# H3_MIDISmallController_Rev_1.net
KiCad netlist of a schematic drawn in EAGLE
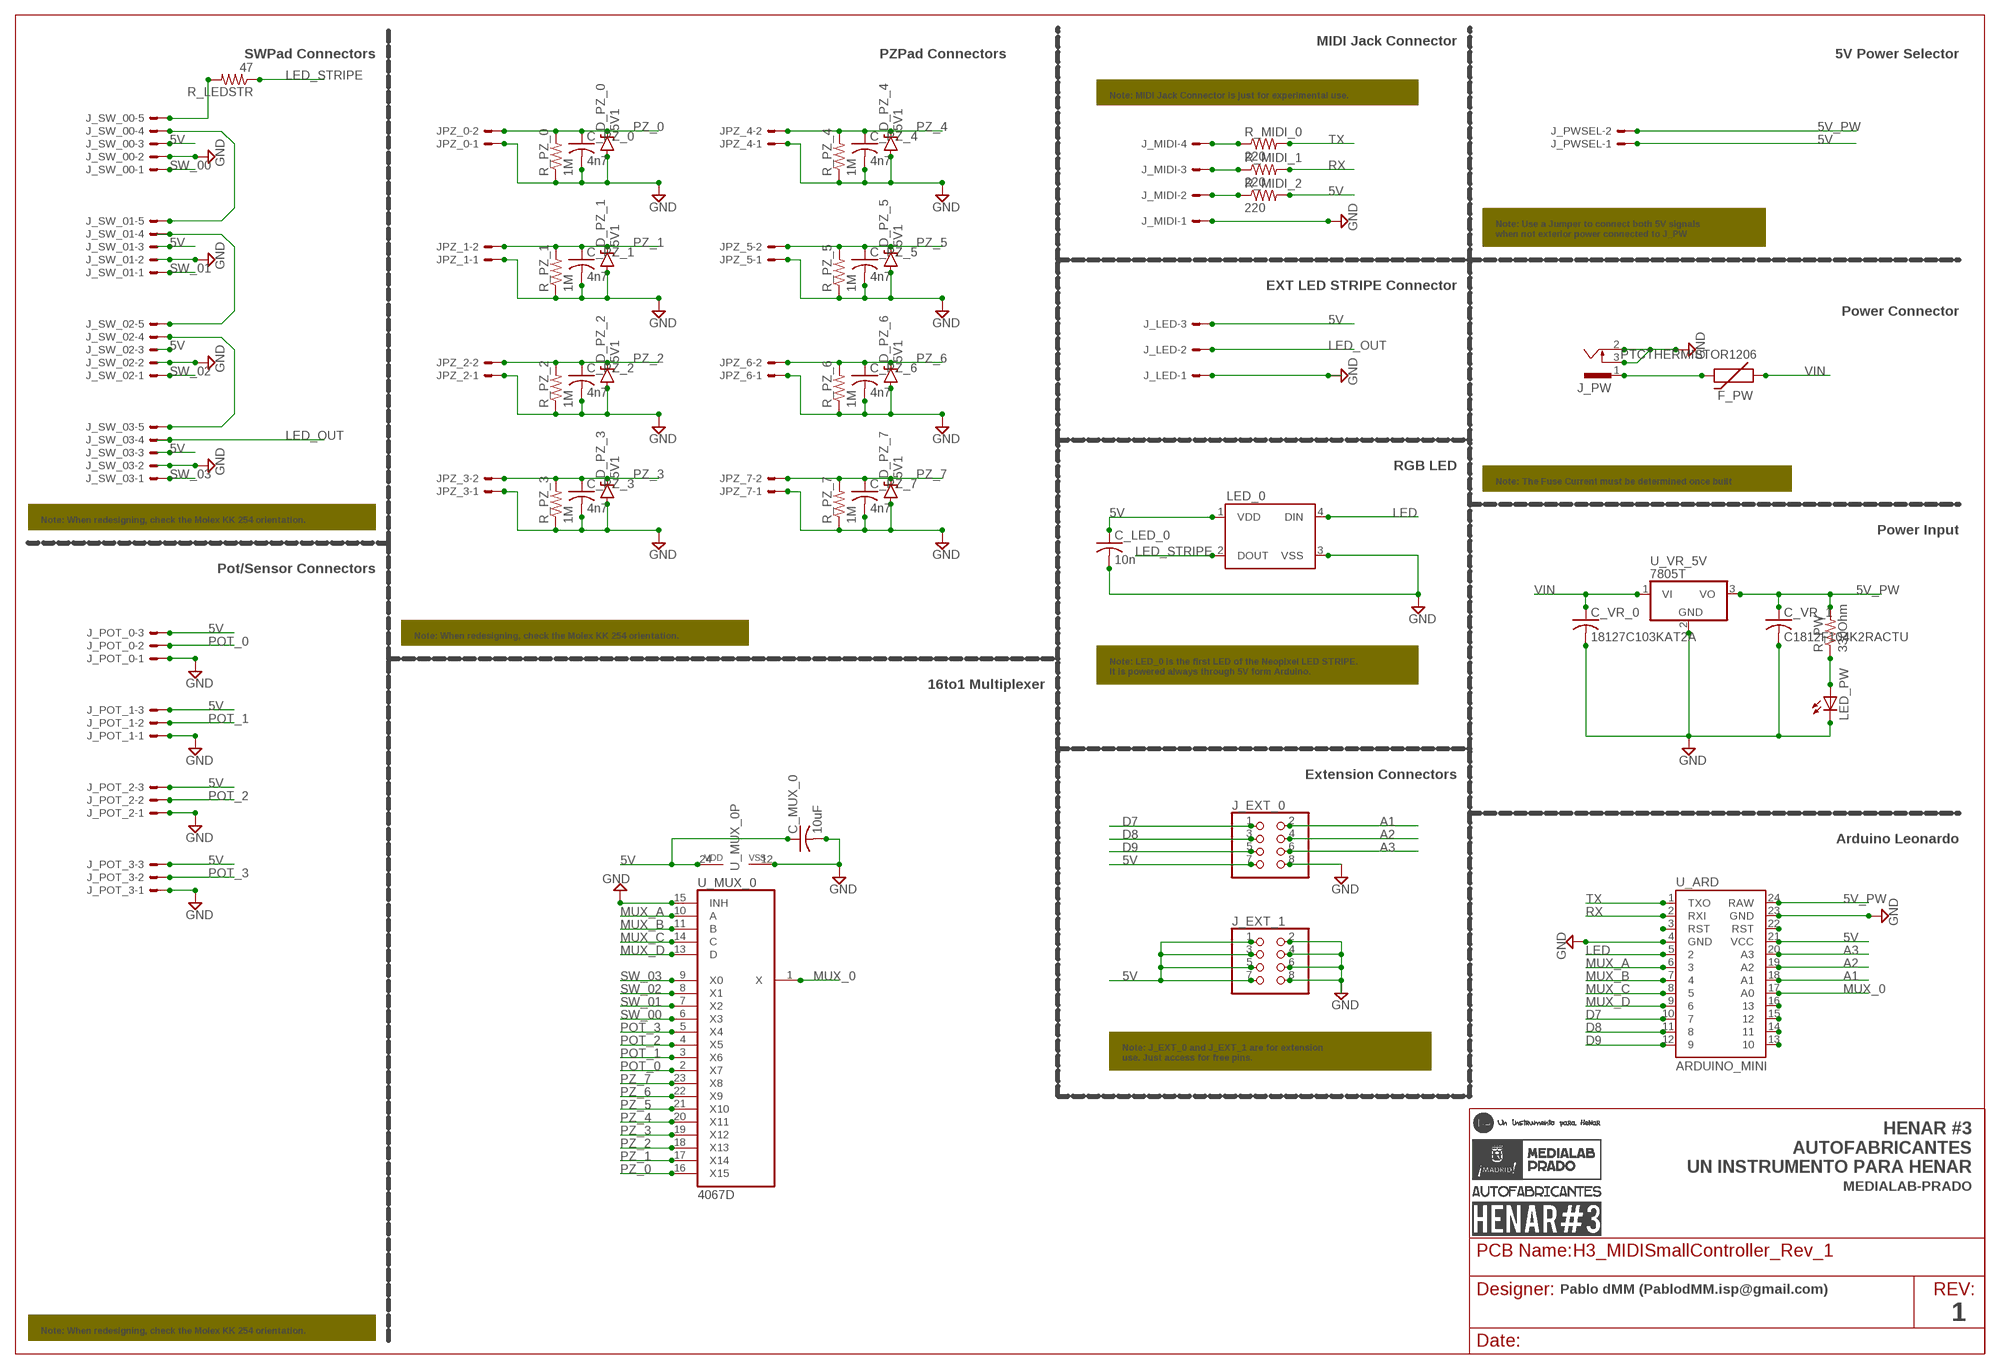
[diagram p0: schematic, sheet 1]

(export (version "E")
  (design (tool "Eeschema 10.0.6"))
  (components
    (comp (ref "C_LED_0")
      (value "10n")
      (footprint "eagle-import:C1206")
      (libsource (lib "eagle-import") (part "C-USC1206"))
    )
    (comp (ref "C_MUX_0")
      (value "10uF")
      (footprint "eagle-import:C1206K")
      (libsource (lib "eagle-import") (part "C-USC1206K"))
    )
    (comp (ref "C_PZ_0")
      (value "4n7")
      (footprint "eagle-import:C1206")
      (libsource (lib "eagle-import") (part "C-USC1206"))
    )
    (comp (ref "C_PZ_1")
      (value "4n7")
      (footprint "eagle-import:C1206")
      (libsource (lib "eagle-import") (part "C-USC1206"))
    )
    (comp (ref "C_PZ_2")
      (value "4n7")
      (footprint "eagle-import:C1206")
      (libsource (lib "eagle-import") (part "C-USC1206"))
    )
    (comp (ref "C_PZ_3")
      (value "4n7")
      (footprint "eagle-import:C1206")
      (libsource (lib "eagle-import") (part "C-USC1206"))
    )
    (comp (ref "C_PZ_4")
      (value "4n7")
      (footprint "eagle-import:C1206")
      (libsource (lib "eagle-import") (part "C-USC1206"))
    )
    (comp (ref "C_PZ_5")
      (value "4n7")
      (footprint "eagle-import:C1206")
      (libsource (lib "eagle-import") (part "C-USC1206"))
    )
    (comp (ref "C_PZ_6")
      (value "4n7")
      (footprint "eagle-import:C1206")
      (libsource (lib "eagle-import") (part "C-USC1206"))
    )
    (comp (ref "C_PZ_7")
      (value "4n7")
      (footprint "eagle-import:C1206")
      (libsource (lib "eagle-import") (part "C-USC1206"))
    )
    (comp (ref "C_VR_0")
      (value "18127C103KAT2A")
      (footprint "eagle-import:C1206")
      (libsource (lib "eagle-import") (part "C-USC1206"))
    )
    (comp (ref "C_VR_1")
      (value "C1812F104K2RACTU")
      (footprint "eagle-import:C1206")
      (libsource (lib "eagle-import") (part "C-USC1206"))
    )
    (comp (ref "D_PZ_0")
      (value "5V1")
      (footprint "eagle-import:DIODE-BZT52")
      (libsource (lib "eagle-import") (part "DIODE-ZENER"))
    )
    (comp (ref "D_PZ_1")
      (value "5V1")
      (footprint "eagle-import:DIODE-BZT52")
      (libsource (lib "eagle-import") (part "DIODE-ZENER"))
    )
    (comp (ref "D_PZ_2")
      (value "5V1")
      (footprint "eagle-import:DIODE-BZT52")
      (libsource (lib "eagle-import") (part "DIODE-ZENER"))
    )
    (comp (ref "D_PZ_3")
      (value "5V1")
      (footprint "eagle-import:DIODE-BZT52")
      (libsource (lib "eagle-import") (part "DIODE-ZENER"))
    )
    (comp (ref "D_PZ_4")
      (value "5V1")
      (footprint "eagle-import:DIODE-BZT52")
      (libsource (lib "eagle-import") (part "DIODE-ZENER"))
    )
    (comp (ref "D_PZ_5")
      (value "5V1")
      (footprint "eagle-import:DIODE-BZT52")
      (libsource (lib "eagle-import") (part "DIODE-ZENER"))
    )
    (comp (ref "D_PZ_6")
      (value "5V1")
      (footprint "eagle-import:DIODE-BZT52")
      (libsource (lib "eagle-import") (part "DIODE-ZENER"))
    )
    (comp (ref "D_PZ_7")
      (value "5V1")
      (footprint "eagle-import:DIODE-BZT52")
      (libsource (lib "eagle-import") (part "DIODE-ZENER"))
    )
    (comp (ref "F_PW")
      (value "PTCTHERMISTOR1206")
      (footprint "eagle-import:PTC-1206")
      (libsource (lib "eagle-import") (part "PTCTHERMISTOR1206"))
    )
    (comp (ref "JPZ_0")
      (value "22-05-7028-02")
      (footprint "eagle-import:7395-02")
      (libsource (lib "eagle-import") (part "22-?-0205-7028"))
    )
    (comp (ref "JPZ_1")
      (value "22-05-7028-02")
      (footprint "eagle-import:7395-02")
      (libsource (lib "eagle-import") (part "22-?-0205-7028"))
    )
    (comp (ref "JPZ_2")
      (value "22-05-7028-02")
      (footprint "eagle-import:7395-02")
      (libsource (lib "eagle-import") (part "22-?-0205-7028"))
    )
    (comp (ref "JPZ_3")
      (value "22-05-7028-02")
      (footprint "eagle-import:7395-02")
      (libsource (lib "eagle-import") (part "22-?-0205-7028"))
    )
    (comp (ref "JPZ_4")
      (value "22-05-7028-02")
      (footprint "eagle-import:7395-02")
      (libsource (lib "eagle-import") (part "22-?-0205-7028"))
    )
    (comp (ref "JPZ_5")
      (value "22-05-7028-02")
      (footprint "eagle-import:7395-02")
      (libsource (lib "eagle-import") (part "22-?-0205-7028"))
    )
    (comp (ref "JPZ_6")
      (value "22-05-7028-02")
      (footprint "eagle-import:7395-02")
      (libsource (lib "eagle-import") (part "22-?-0205-7028"))
    )
    (comp (ref "JPZ_7")
      (value "22-05-7028-02")
      (footprint "eagle-import:7395-02")
      (libsource (lib "eagle-import") (part "22-?-0205-7028"))
    )
    (comp (ref "J_EXT_0")
      (value "PINHD-2X4/90")
      (footprint "eagle-import:2X04_90")
      (libsource (lib "eagle-import") (part "PINHD-2X4/90"))
    )
    (comp (ref "J_EXT_1")
      (value "PINHD-2X4/90")
      (footprint "eagle-import:2X04_90")
      (libsource (lib "eagle-import") (part "PINHD-2X4/90"))
    )
    (comp (ref "J_LED")
      (value "22-05-7038-03")
      (footprint "eagle-import:7395-03")
      (libsource (lib "eagle-import") (part "22-?-0305-7038"))
    )
    (comp (ref "J_MIDI")
      (value "22-05-7048-04")
      (footprint "eagle-import:7395-04")
      (libsource (lib "eagle-import") (part "22-?-0405-7048"))
    )
    (comp (ref "J_POT_0")
      (value "22-05-7038-03")
      (footprint "eagle-import:7395-03")
      (libsource (lib "eagle-import") (part "22-?-0305-7038"))
    )
    (comp (ref "J_POT_1")
      (value "22-05-7038-03")
      (footprint "eagle-import:7395-03")
      (libsource (lib "eagle-import") (part "22-?-0305-7038"))
    )
    (comp (ref "J_POT_2")
      (value "22-05-7038-03")
      (footprint "eagle-import:7395-03")
      (libsource (lib "eagle-import") (part "22-?-0305-7038"))
    )
    (comp (ref "J_POT_3")
      (value "22-05-7038-03")
      (footprint "eagle-import:7395-03")
      (libsource (lib "eagle-import") (part "22-?-0305-7038"))
    )
    (comp (ref "J_PW")
      (value "SCD-014A")
      (footprint "eagle-import:SCD-014-A")
      (libsource (lib "eagle-import") (part "SCD-014A"))
    )
    (comp (ref "J_PWSEL")
      (value "22-05-7028-02")
      (footprint "eagle-import:7395-02")
      (libsource (lib "eagle-import") (part "22-?-0205-7028"))
    )
    (comp (ref "J_SW_00")
      (value "22-05-7058-05")
      (footprint "eagle-import:7395-05")
      (libsource (lib "eagle-import") (part "22-?-0505-7058"))
    )
    (comp (ref "J_SW_01")
      (value "22-05-7058-05")
      (footprint "eagle-import:7395-05")
      (libsource (lib "eagle-import") (part "22-?-0505-7058"))
    )
    (comp (ref "J_SW_02")
      (value "22-05-7058-05")
      (footprint "eagle-import:7395-05")
      (libsource (lib "eagle-import") (part "22-?-0505-7058"))
    )
    (comp (ref "J_SW_03")
      (value "22-05-7058-05")
      (footprint "eagle-import:7395-05")
      (libsource (lib "eagle-import") (part "22-?-0505-7058"))
    )
    (comp (ref "LED_0")
      (value "WS2812B")
      (footprint "eagle-import:WS2812B")
      (libsource (lib "eagle-import") (part "WS2812B"))
    )
    (comp (ref "LED_PW")
      (value "LEDSMT1206")
      (footprint "eagle-import:1206")
      (libsource (lib "eagle-import") (part "LEDSMT1206"))
    )
    (comp (ref "R_LEDSTR")
      (value "47")
      (footprint "eagle-import:M1206")
      (libsource (lib "eagle-import") (part "R-US_M1206"))
    )
    (comp (ref "R_MIDI_0")
      (value "220")
      (footprint "eagle-import:M1206")
      (libsource (lib "eagle-import") (part "R-US_M1206"))
    )
    (comp (ref "R_MIDI_1")
      (value "220")
      (footprint "eagle-import:M1206")
      (libsource (lib "eagle-import") (part "R-US_M1206"))
    )
    (comp (ref "R_MIDI_2")
      (value "220")
      (footprint "eagle-import:M1206")
      (libsource (lib "eagle-import") (part "R-US_M1206"))
    )
    (comp (ref "R_PW")
      (value "330Ohm")
      (footprint "eagle-import:M1206")
      (libsource (lib "eagle-import") (part "R-US_M1206"))
    )
    (comp (ref "R_PZ_0")
      (value "1M")
      (footprint "eagle-import:M1206")
      (libsource (lib "eagle-import") (part "R-US_M1206"))
    )
    (comp (ref "R_PZ_1")
      (value "1M")
      (footprint "eagle-import:M1206")
      (libsource (lib "eagle-import") (part "R-US_M1206"))
    )
    (comp (ref "R_PZ_2")
      (value "1M")
      (footprint "eagle-import:M1206")
      (libsource (lib "eagle-import") (part "R-US_M1206"))
    )
    (comp (ref "R_PZ_3")
      (value "1M")
      (footprint "eagle-import:M1206")
      (libsource (lib "eagle-import") (part "R-US_M1206"))
    )
    (comp (ref "R_PZ_4")
      (value "1M")
      (footprint "eagle-import:M1206")
      (libsource (lib "eagle-import") (part "R-US_M1206"))
    )
    (comp (ref "R_PZ_5")
      (value "1M")
      (footprint "eagle-import:M1206")
      (libsource (lib "eagle-import") (part "R-US_M1206"))
    )
    (comp (ref "R_PZ_6")
      (value "1M")
      (footprint "eagle-import:M1206")
      (libsource (lib "eagle-import") (part "R-US_M1206"))
    )
    (comp (ref "R_PZ_7")
      (value "1M")
      (footprint "eagle-import:M1206")
      (libsource (lib "eagle-import") (part "R-US_M1206"))
    )
    (comp (ref "U_ARD")
      (value "ARDUINO_MINI")
      (footprint "eagle-import:ARDUINO_MINI")
      (libsource (lib "eagle-import") (part "ARDUINO_MINI"))
    )
    (comp (ref "U_MUX_0")
      (value "4067D")
      (footprint "eagle-import:SO24W")
      (libsource (lib "eagle-import") (part "4067D"))
    )
    (comp (ref "U_VR_5V")
      (value "7805T")
      (footprint "eagle-import:TO220H")
      (libsource (lib "eagle-import") (part "78T05"))
    )
  )
  (nets
    (net (code "1") (name "/5V") (class "Default")
      (node (ref "C_LED_0") (pin "1") (pinfunction "1_1") (pintype "passive"))
      (node (ref "C_MUX_0") (pin "1") (pinfunction "1_1") (pintype "passive"))
      (node (ref "J_EXT_0") (pin "7") (pinfunction "7_7") (pintype "passive"))
      (node (ref "J_EXT_1") (pin "1") (pinfunction "1_1") (pintype "passive"))
      (node (ref "J_EXT_1") (pin "3") (pinfunction "3_3") (pintype "passive"))
      (node (ref "J_EXT_1") (pin "5") (pinfunction "5_5") (pintype "passive"))
      (node (ref "J_EXT_1") (pin "7") (pinfunction "7_7") (pintype "passive"))
      (node (ref "J_LED") (pin "3") (pinfunction "S_3") (pintype "passive"))
      (node (ref "J_POT_0") (pin "3") (pinfunction "S_3") (pintype "passive"))
      (node (ref "J_POT_1") (pin "3") (pinfunction "S_3") (pintype "passive"))
      (node (ref "J_POT_2") (pin "3") (pinfunction "S_3") (pintype "passive"))
      (node (ref "J_POT_3") (pin "3") (pinfunction "S_3") (pintype "passive"))
      (node (ref "J_PWSEL") (pin "1") (pinfunction "S_1") (pintype "passive"))
      (node (ref "J_SW_00") (pin "3") (pinfunction "S_3") (pintype "passive"))
      (node (ref "J_SW_01") (pin "3") (pinfunction "S_3") (pintype "passive"))
      (node (ref "J_SW_02") (pin "3") (pinfunction "S_3") (pintype "passive"))
      (node (ref "J_SW_03") (pin "3") (pinfunction "S_3") (pintype "passive"))
      (node (ref "LED_0") (pin "1") (pinfunction "VDD_1") (pintype "power_in"))
      (node (ref "R_MIDI_2") (pin "2") (pinfunction "2_2") (pintype "passive"))
      (node (ref "U_ARD") (pin "21") (pinfunction "VCC_21") (pintype "bidirectional"))
      (node (ref "U_MUX_0") (pin "24") (pinfunction "VDD_24") (pintype "power_in"))
    )
    (net (code "2") (name "/5V_PW") (class "Default")
      (node (ref "C_VR_1") (pin "1") (pinfunction "1_1") (pintype "passive"))
      (node (ref "J_PWSEL") (pin "2") (pinfunction "S_2") (pintype "passive"))
      (node (ref "R_PW") (pin "2") (pinfunction "2_2") (pintype "passive"))
      (node (ref "U_ARD") (pin "24") (pinfunction "RAW_24") (pintype "bidirectional"))
      (node (ref "U_VR_5V") (pin "3") (pinfunction "VO_3") (pintype "passive"))
    )
    (net (code "3") (name "/A1") (class "Default")
      (node (ref "J_EXT_0") (pin "2") (pinfunction "2_2") (pintype "passive"))
      (node (ref "U_ARD") (pin "18") (pinfunction "A1_18") (pintype "bidirectional"))
    )
    (net (code "4") (name "/A2") (class "Default")
      (node (ref "J_EXT_0") (pin "4") (pinfunction "4_4") (pintype "passive"))
      (node (ref "U_ARD") (pin "19") (pinfunction "A2_19") (pintype "bidirectional"))
    )
    (net (code "5") (name "/A3") (class "Default")
      (node (ref "J_EXT_0") (pin "6") (pinfunction "6_6") (pintype "passive"))
      (node (ref "U_ARD") (pin "20") (pinfunction "A3_20") (pintype "bidirectional"))
    )
    (net (code "6") (name "/D7") (class "Default")
      (node (ref "J_EXT_0") (pin "1") (pinfunction "1_1") (pintype "passive"))
      (node (ref "U_ARD") (pin "10") (pinfunction "7_10") (pintype "bidirectional"))
    )
    (net (code "7") (name "/D8") (class "Default")
      (node (ref "J_EXT_0") (pin "3") (pinfunction "3_3") (pintype "passive"))
      (node (ref "U_ARD") (pin "11") (pinfunction "8_11") (pintype "bidirectional"))
    )
    (net (code "8") (name "/D9") (class "Default")
      (node (ref "J_EXT_0") (pin "5") (pinfunction "5_5") (pintype "passive"))
      (node (ref "U_ARD") (pin "12") (pinfunction "9_12") (pintype "bidirectional"))
    )
    (net (code "9") (name "/LED") (class "Default")
      (node (ref "LED_0") (pin "4") (pinfunction "DIN_4") (pintype "input"))
      (node (ref "U_ARD") (pin "5") (pinfunction "2_5") (pintype "bidirectional"))
    )
    (net (code "10") (name "/LED_OUT") (class "Default")
      (node (ref "J_LED") (pin "2") (pinfunction "S_2") (pintype "passive"))
      (node (ref "J_SW_03") (pin "4") (pinfunction "S_4") (pintype "passive"))
    )
    (net (code "11") (name "/LED_STRIPE") (class "Default")
      (node (ref "LED_0") (pin "2") (pinfunction "DOUT_2") (pintype "output"))
      (node (ref "R_LEDSTR") (pin "1") (pinfunction "1_1") (pintype "passive"))
    )
    (net (code "12") (name "/MUX_0") (class "Default")
      (node (ref "U_ARD") (pin "17") (pinfunction "A0_17") (pintype "bidirectional"))
      (node (ref "U_MUX_0") (pin "1") (pinfunction "X_1") (pintype "output"))
    )
    (net (code "13") (name "/MUX_A") (class "Default")
      (node (ref "U_ARD") (pin "6") (pinfunction "3_6") (pintype "bidirectional"))
      (node (ref "U_MUX_0") (pin "10") (pinfunction "A_10") (pintype "input"))
    )
    (net (code "14") (name "/MUX_B") (class "Default")
      (node (ref "U_ARD") (pin "7") (pinfunction "4_7") (pintype "bidirectional"))
      (node (ref "U_MUX_0") (pin "11") (pinfunction "B_11") (pintype "input"))
    )
    (net (code "15") (name "/MUX_C") (class "Default")
      (node (ref "U_ARD") (pin "8") (pinfunction "5_8") (pintype "bidirectional"))
      (node (ref "U_MUX_0") (pin "14") (pinfunction "C_14") (pintype "input"))
    )
    (net (code "16") (name "/MUX_D") (class "Default")
      (node (ref "U_ARD") (pin "9") (pinfunction "6_9") (pintype "bidirectional"))
      (node (ref "U_MUX_0") (pin "13") (pinfunction "D_13") (pintype "input"))
    )
    (net (code "17") (name "/POT_0") (class "Default")
      (node (ref "J_POT_0") (pin "2") (pinfunction "S_2") (pintype "passive"))
      (node (ref "U_MUX_0") (pin "2") (pinfunction "X7_2") (pintype "input"))
    )
    (net (code "18") (name "/POT_1") (class "Default")
      (node (ref "J_POT_1") (pin "2") (pinfunction "S_2") (pintype "passive"))
      (node (ref "U_MUX_0") (pin "3") (pinfunction "X6_3") (pintype "input"))
    )
    (net (code "19") (name "/POT_2") (class "Default")
      (node (ref "J_POT_2") (pin "2") (pinfunction "S_2") (pintype "passive"))
      (node (ref "U_MUX_0") (pin "4") (pinfunction "X5_4") (pintype "input"))
    )
    (net (code "20") (name "/POT_3") (class "Default")
      (node (ref "J_POT_3") (pin "2") (pinfunction "S_2") (pintype "passive"))
      (node (ref "U_MUX_0") (pin "5") (pinfunction "X4_5") (pintype "input"))
    )
    (net (code "21") (name "/PZ_0") (class "Default")
      (node (ref "C_PZ_0") (pin "1") (pinfunction "1_1") (pintype "passive"))
      (node (ref "D_PZ_0") (pin "C") (pinfunction "C_C") (pintype "passive"))
      (node (ref "JPZ_0") (pin "2") (pinfunction "S_2") (pintype "passive"))
      (node (ref "R_PZ_0") (pin "2") (pinfunction "2_2") (pintype "passive"))
      (node (ref "U_MUX_0") (pin "16") (pinfunction "X15_16") (pintype "input"))
    )
    (net (code "22") (name "/PZ_1") (class "Default")
      (node (ref "C_PZ_1") (pin "1") (pinfunction "1_1") (pintype "passive"))
      (node (ref "D_PZ_1") (pin "C") (pinfunction "C_C") (pintype "passive"))
      (node (ref "JPZ_1") (pin "2") (pinfunction "S_2") (pintype "passive"))
      (node (ref "R_PZ_1") (pin "2") (pinfunction "2_2") (pintype "passive"))
      (node (ref "U_MUX_0") (pin "17") (pinfunction "X14_17") (pintype "input"))
    )
    (net (code "23") (name "/PZ_2") (class "Default")
      (node (ref "C_PZ_2") (pin "1") (pinfunction "1_1") (pintype "passive"))
      (node (ref "D_PZ_2") (pin "C") (pinfunction "C_C") (pintype "passive"))
      (node (ref "JPZ_2") (pin "2") (pinfunction "S_2") (pintype "passive"))
      (node (ref "R_PZ_2") (pin "2") (pinfunction "2_2") (pintype "passive"))
      (node (ref "U_MUX_0") (pin "18") (pinfunction "X13_18") (pintype "input"))
    )
    (net (code "24") (name "/PZ_3") (class "Default")
      (node (ref "C_PZ_3") (pin "1") (pinfunction "1_1") (pintype "passive"))
      (node (ref "D_PZ_3") (pin "C") (pinfunction "C_C") (pintype "passive"))
      (node (ref "JPZ_3") (pin "2") (pinfunction "S_2") (pintype "passive"))
      (node (ref "R_PZ_3") (pin "2") (pinfunction "2_2") (pintype "passive"))
      (node (ref "U_MUX_0") (pin "19") (pinfunction "X12_19") (pintype "input"))
    )
    (net (code "25") (name "/PZ_4") (class "Default")
      (node (ref "C_PZ_4") (pin "1") (pinfunction "1_1") (pintype "passive"))
      (node (ref "D_PZ_4") (pin "C") (pinfunction "C_C") (pintype "passive"))
      (node (ref "JPZ_4") (pin "2") (pinfunction "S_2") (pintype "passive"))
      (node (ref "R_PZ_4") (pin "2") (pinfunction "2_2") (pintype "passive"))
      (node (ref "U_MUX_0") (pin "20") (pinfunction "X11_20") (pintype "input"))
    )
    (net (code "26") (name "/PZ_5") (class "Default")
      (node (ref "C_PZ_5") (pin "1") (pinfunction "1_1") (pintype "passive"))
      (node (ref "D_PZ_5") (pin "C") (pinfunction "C_C") (pintype "passive"))
      (node (ref "JPZ_5") (pin "2") (pinfunction "S_2") (pintype "passive"))
      (node (ref "R_PZ_5") (pin "2") (pinfunction "2_2") (pintype "passive"))
      (node (ref "U_MUX_0") (pin "21") (pinfunction "X10_21") (pintype "input"))
    )
    (net (code "27") (name "/PZ_6") (class "Default")
      (node (ref "C_PZ_6") (pin "1") (pinfunction "1_1") (pintype "passive"))
      (node (ref "D_PZ_6") (pin "C") (pinfunction "C_C") (pintype "passive"))
      (node (ref "JPZ_6") (pin "2") (pinfunction "S_2") (pintype "passive"))
      (node (ref "R_PZ_6") (pin "2") (pinfunction "2_2") (pintype "passive"))
      (node (ref "U_MUX_0") (pin "22") (pinfunction "X9_22") (pintype "input"))
    )
    (net (code "28") (name "/PZ_7") (class "Default")
      (node (ref "C_PZ_7") (pin "1") (pinfunction "1_1") (pintype "passive"))
      (node (ref "D_PZ_7") (pin "C") (pinfunction "C_C") (pintype "passive"))
      (node (ref "JPZ_7") (pin "2") (pinfunction "S_2") (pintype "passive"))
      (node (ref "R_PZ_7") (pin "2") (pinfunction "2_2") (pintype "passive"))
      (node (ref "U_MUX_0") (pin "23") (pinfunction "X8_23") (pintype "input"))
    )
    (net (code "29") (name "/RX") (class "Default")
      (node (ref "R_MIDI_1") (pin "2") (pinfunction "2_2") (pintype "passive"))
      (node (ref "U_ARD") (pin "2") (pinfunction "RXI_2") (pintype "bidirectional"))
    )
    (net (code "30") (name "/SW_00") (class "Default")
      (node (ref "J_SW_00") (pin "1") (pinfunction "S_1") (pintype "passive"))
      (node (ref "U_MUX_0") (pin "6") (pinfunction "X3_6") (pintype "input"))
    )
    (net (code "31") (name "/SW_01") (class "Default")
      (node (ref "J_SW_01") (pin "1") (pinfunction "S_1") (pintype "passive"))
      (node (ref "U_MUX_0") (pin "7") (pinfunction "X2_7") (pintype "input"))
    )
    (net (code "32") (name "/SW_02") (class "Default")
      (node (ref "J_SW_02") (pin "1") (pinfunction "S_1") (pintype "passive"))
      (node (ref "U_MUX_0") (pin "8") (pinfunction "X1_8") (pintype "input"))
    )
    (net (code "33") (name "/SW_03") (class "Default")
      (node (ref "J_SW_03") (pin "1") (pinfunction "S_1") (pintype "passive"))
      (node (ref "U_MUX_0") (pin "9") (pinfunction "X0_9") (pintype "input"))
    )
    (net (code "34") (name "/TX") (class "Default")
      (node (ref "R_MIDI_0") (pin "2") (pinfunction "2_2") (pintype "passive"))
      (node (ref "U_ARD") (pin "1") (pinfunction "TXO_1") (pintype "bidirectional"))
    )
    (net (code "35") (name "/VIN") (class "Default")
      (node (ref "C_VR_0") (pin "1") (pinfunction "1_1") (pintype "passive"))
      (node (ref "F_PW") (pin "1") (pinfunction "1_1") (pintype "bidirectional"))
      (node (ref "U_VR_5V") (pin "1") (pinfunction "VI_1") (pintype "input"))
    )
    (net (code "36") (name "GND") (class "Default")
      (node (ref "C_LED_0") (pin "2") (pinfunction "2_2") (pintype "passive"))
      (node (ref "C_MUX_0") (pin "2") (pinfunction "2_2") (pintype "passive"))
      (node (ref "C_PZ_0") (pin "2") (pinfunction "2_2") (pintype "passive"))
      (node (ref "C_PZ_1") (pin "2") (pinfunction "2_2") (pintype "passive"))
      (node (ref "C_PZ_2") (pin "2") (pinfunction "2_2") (pintype "passive"))
      (node (ref "C_PZ_3") (pin "2") (pinfunction "2_2") (pintype "passive"))
      (node (ref "C_PZ_4") (pin "2") (pinfunction "2_2") (pintype "passive"))
      (node (ref "C_PZ_5") (pin "2") (pinfunction "2_2") (pintype "passive"))
      (node (ref "C_PZ_6") (pin "2") (pinfunction "2_2") (pintype "passive"))
      (node (ref "C_PZ_7") (pin "2") (pinfunction "2_2") (pintype "passive"))
      (node (ref "C_VR_0") (pin "2") (pinfunction "2_2") (pintype "passive"))
      (node (ref "C_VR_1") (pin "2") (pinfunction "2_2") (pintype "passive"))
      (node (ref "D_PZ_0") (pin "A") (pinfunction "A_A") (pintype "passive"))
      (node (ref "D_PZ_1") (pin "A") (pinfunction "A_A") (pintype "passive"))
      (node (ref "D_PZ_2") (pin "A") (pinfunction "A_A") (pintype "passive"))
      (node (ref "D_PZ_3") (pin "A") (pinfunction "A_A") (pintype "passive"))
      (node (ref "D_PZ_4") (pin "A") (pinfunction "A_A") (pintype "passive"))
      (node (ref "D_PZ_5") (pin "A") (pinfunction "A_A") (pintype "passive"))
      (node (ref "D_PZ_6") (pin "A") (pinfunction "A_A") (pintype "passive"))
      (node (ref "D_PZ_7") (pin "A") (pinfunction "A_A") (pintype "passive"))
      (node (ref "JPZ_0") (pin "1") (pinfunction "S_1") (pintype "passive"))
      (node (ref "JPZ_1") (pin "1") (pinfunction "S_1") (pintype "passive"))
      (node (ref "JPZ_2") (pin "1") (pinfunction "S_1") (pintype "passive"))
      (node (ref "JPZ_3") (pin "1") (pinfunction "S_1") (pintype "passive"))
      (node (ref "JPZ_4") (pin "1") (pinfunction "S_1") (pintype "passive"))
      (node (ref "JPZ_5") (pin "1") (pinfunction "S_1") (pintype "passive"))
      (node (ref "JPZ_6") (pin "1") (pinfunction "S_1") (pintype "passive"))
      (node (ref "JPZ_7") (pin "1") (pinfunction "S_1") (pintype "passive"))
      (node (ref "J_EXT_0") (pin "8") (pinfunction "8_8") (pintype "passive"))
      (node (ref "J_EXT_1") (pin "2") (pinfunction "2_2") (pintype "passive"))
      (node (ref "J_EXT_1") (pin "4") (pinfunction "4_4") (pintype "passive"))
      (node (ref "J_EXT_1") (pin "6") (pinfunction "6_6") (pintype "passive"))
      (node (ref "J_EXT_1") (pin "8") (pinfunction "8_8") (pintype "passive"))
      (node (ref "J_LED") (pin "1") (pinfunction "S_1") (pintype "passive"))
      (node (ref "J_MIDI") (pin "1") (pinfunction "S_1") (pintype "passive"))
      (node (ref "J_POT_0") (pin "1") (pinfunction "S_1") (pintype "passive"))
      (node (ref "J_POT_1") (pin "1") (pinfunction "S_1") (pintype "passive"))
      (node (ref "J_POT_2") (pin "1") (pinfunction "S_1") (pintype "passive"))
      (node (ref "J_POT_3") (pin "1") (pinfunction "S_1") (pintype "passive"))
      (node (ref "J_PW") (pin "2") (pinfunction "2_2") (pintype "passive"))
      (node (ref "J_PW") (pin "3") (pinfunction "3_3") (pintype "passive"))
      (node (ref "J_SW_00") (pin "2") (pinfunction "S_2") (pintype "passive"))
      (node (ref "J_SW_01") (pin "2") (pinfunction "S_2") (pintype "passive"))
      (node (ref "J_SW_02") (pin "2") (pinfunction "S_2") (pintype "passive"))
      (node (ref "J_SW_03") (pin "2") (pinfunction "S_2") (pintype "passive"))
      (node (ref "LED_0") (pin "3") (pinfunction "VSS_3") (pintype "power_in"))
      (node (ref "LED_PW") (pin "C") (pinfunction "C_C") (pintype "passive"))
      (node (ref "R_PZ_0") (pin "1") (pinfunction "1_1") (pintype "passive"))
      (node (ref "R_PZ_1") (pin "1") (pinfunction "1_1") (pintype "passive"))
      (node (ref "R_PZ_2") (pin "1") (pinfunction "1_1") (pintype "passive"))
      (node (ref "R_PZ_3") (pin "1") (pinfunction "1_1") (pintype "passive"))
      (node (ref "R_PZ_4") (pin "1") (pinfunction "1_1") (pintype "passive"))
      (node (ref "R_PZ_5") (pin "1") (pinfunction "1_1") (pintype "passive"))
      (node (ref "R_PZ_6") (pin "1") (pinfunction "1_1") (pintype "passive"))
      (node (ref "R_PZ_7") (pin "1") (pinfunction "1_1") (pintype "passive"))
      (node (ref "U_ARD") (pin "23") (pinfunction "GND_23") (pintype "bidirectional"))
      (node (ref "U_ARD") (pin "4") (pinfunction "GND_4") (pintype "bidirectional"))
      (node (ref "U_MUX_0") (pin "12") (pinfunction "VSS_12") (pintype "power_in"))
      (node (ref "U_MUX_0") (pin "15") (pinfunction "INH_15") (pintype "input"))
      (node (ref "U_VR_5V") (pin "2") (pinfunction "GND_2") (pintype "passive"))
    )
    (net (code "37") (name "Net-(F_PW-Pad2)") (class "Default")
      (node (ref "F_PW") (pin "2") (pinfunction "2_2") (pintype "bidirectional"))
      (node (ref "J_PW") (pin "1") (pinfunction "1_1") (pintype "passive"))
    )
    (net (code "38") (name "Net-(J_MIDIB-S)") (class "Default")
      (node (ref "J_MIDI") (pin "2") (pinfunction "S_2") (pintype "passive"))
      (node (ref "R_MIDI_2") (pin "1") (pinfunction "1_1") (pintype "passive"))
    )
    (net (code "39") (name "Net-(J_MIDIC-S)") (class "Default")
      (node (ref "J_MIDI") (pin "3") (pinfunction "S_3") (pintype "passive"))
      (node (ref "R_MIDI_1") (pin "1") (pinfunction "1_1") (pintype "passive"))
    )
    (net (code "40") (name "Net-(J_MIDID-S)") (class "Default")
      (node (ref "J_MIDI") (pin "4") (pinfunction "S_4") (pintype "passive"))
      (node (ref "R_MIDI_0") (pin "1") (pinfunction "1_1") (pintype "passive"))
    )
    (net (code "41") (name "Net-(J_SW_00D-S)") (class "Default")
      (node (ref "J_SW_00") (pin "4") (pinfunction "S_4") (pintype "passive"))
      (node (ref "J_SW_01") (pin "5") (pinfunction "S_5") (pintype "passive"))
    )
    (net (code "42") (name "Net-(J_SW_00E-S)") (class "Default")
      (node (ref "J_SW_00") (pin "5") (pinfunction "S_5") (pintype "passive"))
      (node (ref "R_LEDSTR") (pin "2") (pinfunction "2_2") (pintype "passive"))
    )
    (net (code "43") (name "Net-(J_SW_01D-S)") (class "Default")
      (node (ref "J_SW_01") (pin "4") (pinfunction "S_4") (pintype "passive"))
      (node (ref "J_SW_02") (pin "5") (pinfunction "S_5") (pintype "passive"))
    )
    (net (code "44") (name "Net-(J_SW_02D-S)") (class "Default")
      (node (ref "J_SW_02") (pin "4") (pinfunction "S_4") (pintype "passive"))
      (node (ref "J_SW_03") (pin "5") (pinfunction "S_5") (pintype "passive"))
    )
    (net (code "45") (name "Net-(LED_PW-PadA)") (class "Default")
      (node (ref "LED_PW") (pin "A") (pinfunction "A_A") (pintype "passive"))
      (node (ref "R_PW") (pin "1") (pinfunction "1_1") (pintype "passive"))
    )
    (net (code "46") (name "unconnected-(U_ARD-10-Pad13)") (class "Default")
      (node (ref "U_ARD") (pin "13") (pinfunction "10_13") (pintype "bidirectional"))
    )
    (net (code "47") (name "unconnected-(U_ARD-11-Pad14)") (class "Default")
      (node (ref "U_ARD") (pin "14") (pinfunction "11_14") (pintype "bidirectional"))
    )
    (net (code "48") (name "unconnected-(U_ARD-12-Pad15)") (class "Default")
      (node (ref "U_ARD") (pin "15") (pinfunction "12_15") (pintype "bidirectional"))
    )
    (net (code "49") (name "unconnected-(U_ARD-13-Pad16)") (class "Default")
      (node (ref "U_ARD") (pin "16") (pinfunction "13_16") (pintype "bidirectional"))
    )
    (net (code "50") (name "unconnected-(U_ARD-RST-Pad3)") (class "Default")
      (node (ref "U_ARD") (pin "3") (pinfunction "RST_3") (pintype "bidirectional"))
    )
    (net (code "51") (name "unconnected-(U_ARD-RST-Pad22)") (class "Default")
      (node (ref "U_ARD") (pin "22") (pinfunction "RST_22") (pintype "bidirectional"))
    )
  )
)
